# kolrs868_tx_1_4.net
KiCad netlist of a schematic drawn in EAGLE
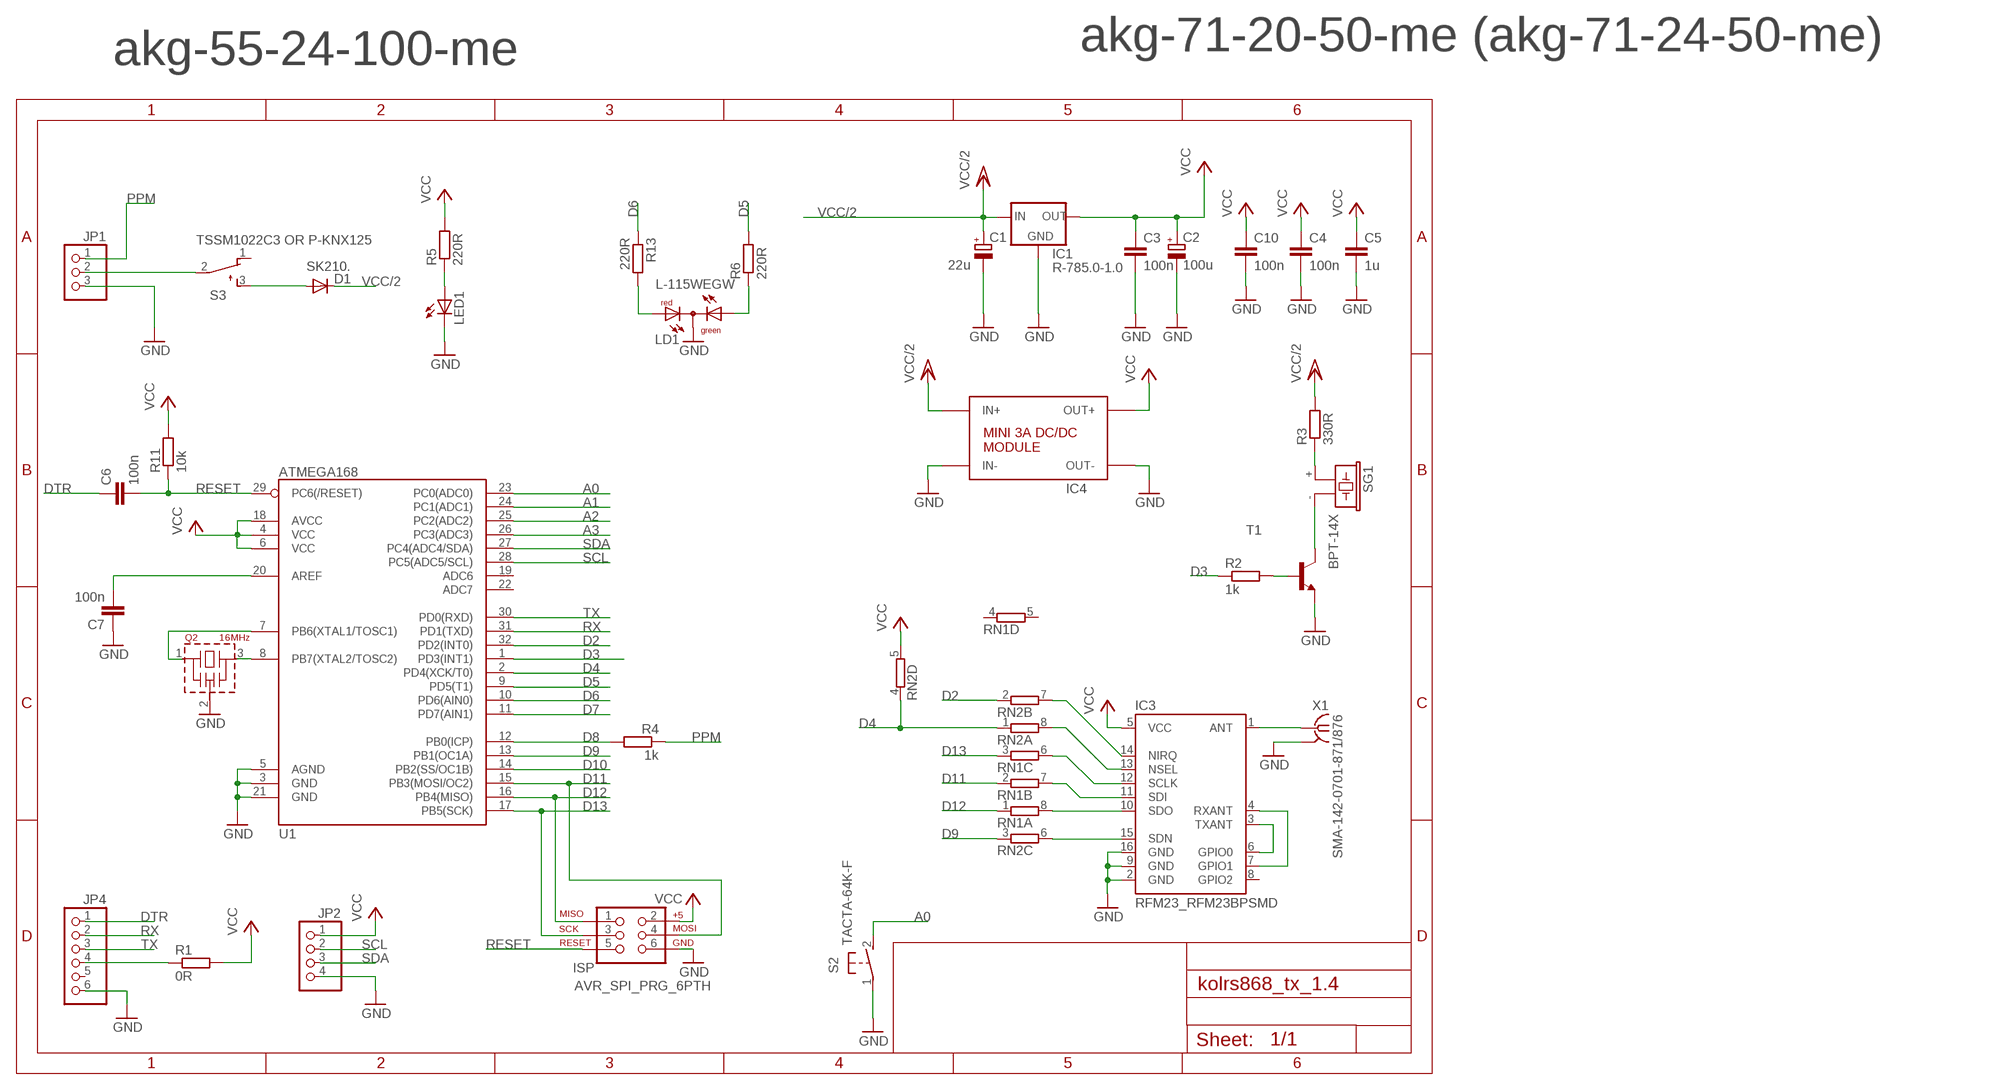
[diagram p0: schematic, sheet 1]

(export (version "E")
  (design (tool "Eeschema 10.0.6"))
  (components
    (comp (ref "C1")
      (value "22u")
      (footprint "eagle-import:SMC_B")
      (libsource (lib "eagle-import") (part "CPOL-EUSMCB"))
    )
    (comp (ref "C2")
      (value "100u")
      (footprint "eagle-import:SMC_B")
      (libsource (lib "eagle-import") (part "CPOL-EUSMCB"))
    )
    (comp (ref "C3")
      (value "100n")
      (footprint "eagle-import:M0805")
      (libsource (lib "eagle-import") (part "C-EU_KOLIN"))
    )
    (comp (ref "C4")
      (value "100n")
      (footprint "eagle-import:M0805")
      (libsource (lib "eagle-import") (part "C-EU_KOLIN"))
    )
    (comp (ref "C5")
      (value "1u")
      (footprint "eagle-import:C1206")
      (libsource (lib "eagle-import") (part "C-EUC1206"))
    )
    (comp (ref "C6")
      (value "100n")
      (footprint "eagle-import:M0805")
      (libsource (lib "eagle-import") (part "C-EU_KOLIN"))
    )
    (comp (ref "C7")
      (value "100n")
      (footprint "eagle-import:M0805")
      (libsource (lib "eagle-import") (part "C-EU_KOLIN"))
    )
    (comp (ref "C10")
      (value "100n")
      (footprint "eagle-import:M0805")
      (libsource (lib "eagle-import") (part "C-EU_KOLIN"))
    )
    (comp (ref "D1")
      (value "SK210.")
      (footprint "eagle-import:SMB")
      (libsource (lib "eagle-import") (part "DIODE-SMB"))
    )
    (comp (ref "IC1")
      (value "R-785.0-1.0")
      (footprint "eagle-import:78XX_RECOM")
      (libsource (lib "eagle-import") (part "78XX_RECOM"))
    )
    (comp (ref "IC3")
      (value "RFM23_RFM23BPSMD")
      (footprint "eagle-import:RFM23_RFM23BP-S2")
      (libsource (lib "eagle-import") (part "RFM23_RFM23BPSMD"))
    )
    (comp (ref "IC4")
      (value "MINI_3A_DCDC")
      (footprint "eagle-import:MINI_3A_DCDC")
      (libsource (lib "eagle-import") (part "MINI_3A_DCDC"))
    )
    (comp (ref "ISP")
      (value "AVR_SPI_PRG_6PTH")
      (footprint "eagle-import:2X3")
      (libsource (lib "eagle-import") (part "AVR_SPI_PRG_6PTH"))
    )
    (comp (ref "JP1")
      (value "PINHD-1X3")
      (footprint "eagle-import:1X03")
      (libsource (lib "eagle-import") (part "PINHD-1X3"))
    )
    (comp (ref "JP2")
      (value "PINHD-1X4")
      (footprint "eagle-import:1X04")
      (libsource (lib "eagle-import") (part "PINHD-1X4"))
    )
    (comp (ref "JP4")
      (value "PINHD-1X6")
      (footprint "eagle-import:1X06")
      (libsource (lib "eagle-import") (part "PINHD-1X6"))
    )
    (comp (ref "LD1")
      (value "L-115WEGW")
      (footprint "eagle-import:DUOLED-C-5MM")
      (libsource (lib "eagle-import") (part "DUOLED-RG-C"))
    )
    (comp (ref "LED1")
      (value "LEDCHIPLED_1206")
      (footprint "eagle-import:CHIPLED_1206")
      (libsource (lib "eagle-import") (part "LEDCHIPLED_1206"))
    )
    (comp (ref "Q2")
      (value "16MHz")
      (footprint "eagle-import:CSTLS_G9")
      (libsource (lib "eagle-import") (part "murata-resonators_CSTLS_G"))
    )
    (comp (ref "R1")
      (value "0R")
      (footprint "eagle-import:M0805")
      (libsource (lib "eagle-import") (part "R-EU_KOLINM0805"))
    )
    (comp (ref "R2")
      (value "1k")
      (footprint "eagle-import:M0805")
      (libsource (lib "eagle-import") (part "R-EU_KOLINM0805"))
    )
    (comp (ref "R3")
      (value "330R")
      (footprint "eagle-import:M0805")
      (libsource (lib "eagle-import") (part "R-EU_KOLINM0805"))
    )
    (comp (ref "R4")
      (value "1k")
      (footprint "eagle-import:M0805")
      (libsource (lib "eagle-import") (part "R-EU_KOLINM0805"))
    )
    (comp (ref "R5")
      (value "220R")
      (footprint "eagle-import:M0805")
      (libsource (lib "eagle-import") (part "R-EU_KOLINM0805"))
    )
    (comp (ref "R6")
      (value "220R")
      (footprint "eagle-import:M0805")
      (libsource (lib "eagle-import") (part "R-EU_KOLINM0805"))
    )
    (comp (ref "R11")
      (value "10k")
      (footprint "eagle-import:M0805")
      (libsource (lib "eagle-import") (part "R-EU_KOLINM0805"))
    )
    (comp (ref "R13")
      (value "220R")
      (footprint "eagle-import:M0805")
      (libsource (lib "eagle-import") (part "R-EU_KOLINM0805"))
    )
    (comp (ref "RN1")
      (value "4R-NCAY16")
      (footprint "eagle-import:CAY16")
      (libsource (lib "eagle-import") (part "4R-NCAY16"))
    )
    (comp (ref "RN2")
      (value "4R-NCAY16")
      (footprint "eagle-import:CAY16")
      (fields (field (name "OC_FARNELL") "unknown") (field (name "OC_NEWARK") "unknown"))
      (libsource (lib "eagle-import") (part "4R-NCAY16"))
    )
    (comp (ref "S2")
      (value "TACTA-64K-F")
      (footprint "eagle-import:B3F-31XX")
      (fields (field (name "MPN") "B3F-3100"))
      (libsource (lib "eagle-import") (part "31-XX"))
    )
    (comp (ref "S3")
      (value "TSSM1022C3 OR P-KNX125")
      (footprint "eagle-import:TL3XWO")
      (libsource (lib "eagle-import") (part "TL32WO"))
    )
    (comp (ref "SG1")
      (value "BPT-14X")
      (footprint "eagle-import:F_CM12P")
      (libsource (lib "eagle-import") (part "F/CM12P"))
    )
    (comp (ref "T1")
      (value "BC848-NPN-SOT23-BEC")
      (footprint "eagle-import:SOT23-BEC")
      (libsource (lib "eagle-import") (part "-NPN-SOT23-BECBC848"))
    )
    (comp (ref "U1")
      (value "ATMEGA168")
      (footprint "eagle-import:TQFP32-08")
      (libsource (lib "eagle-import") (part "ATMEGA168"))
    )
    (comp (ref "X1")
      (value "SMA-142-0701-871/876")
      (footprint "eagle-import:J502-ND-142-0701-871_876")
      (fields (field (name "MF") "JOHNSON COMPONENTS") (field (name "MPN") "142-0701-871"))
      (libsource (lib "eagle-import") (part "SMA-142-0701-871/876"))
    )
  )
  (nets
    (net (code "1") (name "/A0") (class "Default")
      (node (ref "S2") (pin "2") (pinfunction "S_2") (pintype "passive"))
      (node (ref "U1") (pin "23") (pinfunction "PC0(ADC0)_23") (pintype "bidirectional"))
    )
    (net (code "2") (name "/A1") (class "Default")
      (node (ref "U1") (pin "24") (pinfunction "PC1(ADC1)_24") (pintype "bidirectional"))
    )
    (net (code "3") (name "/A2") (class "Default")
      (node (ref "U1") (pin "25") (pinfunction "PC2(ADC2)_25") (pintype "bidirectional"))
    )
    (net (code "4") (name "/A3") (class "Default")
      (node (ref "U1") (pin "26") (pinfunction "PC3(ADC3)_26") (pintype "bidirectional"))
    )
    (net (code "5") (name "/D2") (class "Default")
      (node (ref "RN2") (pin "2") (pinfunction "1_2") (pintype "passive"))
      (node (ref "U1") (pin "32") (pinfunction "PD2(INT0)_32") (pintype "bidirectional"))
    )
    (net (code "6") (name "/D3") (class "Default")
      (node (ref "R2") (pin "1") (pinfunction "1_1") (pintype "passive"))
      (node (ref "U1") (pin "1") (pinfunction "PD3(INT1)_1") (pintype "bidirectional"))
    )
    (net (code "7") (name "/D4") (class "Default")
      (node (ref "RN2") (pin "1") (pinfunction "1_1") (pintype "passive"))
      (node (ref "RN2") (pin "4") (pinfunction "1_4") (pintype "passive"))
      (node (ref "U1") (pin "2") (pinfunction "PD4(XCK/T0)_2") (pintype "bidirectional"))
    )
    (net (code "8") (name "/D5") (class "Default")
      (node (ref "R6") (pin "2") (pinfunction "2_2") (pintype "passive"))
      (node (ref "U1") (pin "9") (pinfunction "PD5(T1)_9") (pintype "bidirectional"))
    )
    (net (code "9") (name "/D6") (class "Default")
      (node (ref "R13") (pin "1") (pinfunction "1_1") (pintype "passive"))
      (node (ref "U1") (pin "10") (pinfunction "PD6(AIN0)_10") (pintype "bidirectional"))
    )
    (net (code "10") (name "/D7") (class "Default")
      (node (ref "U1") (pin "11") (pinfunction "PD7(AIN1)_11") (pintype "bidirectional"))
    )
    (net (code "11") (name "/D8") (class "Default")
      (node (ref "R4") (pin "2") (pinfunction "2_2") (pintype "passive"))
      (node (ref "U1") (pin "12") (pinfunction "PB0(ICP)_12") (pintype "bidirectional"))
    )
    (net (code "12") (name "/D9") (class "Default")
      (node (ref "RN2") (pin "3") (pinfunction "1_3") (pintype "passive"))
      (node (ref "U1") (pin "13") (pinfunction "PB1(OC1A)_13") (pintype "bidirectional"))
    )
    (net (code "13") (name "/D10") (class "Default")
      (node (ref "U1") (pin "14") (pinfunction "PB2(SS/OC1B)_14") (pintype "bidirectional"))
    )
    (net (code "14") (name "/D11") (class "Default")
      (node (ref "ISP") (pin "4") (pinfunction "4_4") (pintype "passive"))
      (node (ref "RN1") (pin "2") (pinfunction "1_2") (pintype "passive"))
      (node (ref "U1") (pin "15") (pinfunction "PB3(MOSI/OC2)_15") (pintype "bidirectional"))
    )
    (net (code "15") (name "/D12") (class "Default")
      (node (ref "ISP") (pin "1") (pinfunction "1_1") (pintype "passive"))
      (node (ref "RN1") (pin "1") (pinfunction "1_1") (pintype "passive"))
      (node (ref "U1") (pin "16") (pinfunction "PB4(MISO)_16") (pintype "bidirectional"))
    )
    (net (code "16") (name "/D13") (class "Default")
      (node (ref "ISP") (pin "3") (pinfunction "3_3") (pintype "passive"))
      (node (ref "RN1") (pin "3") (pinfunction "1_3") (pintype "passive"))
      (node (ref "U1") (pin "17") (pinfunction "PB5(SCK)_17") (pintype "bidirectional"))
    )
    (net (code "17") (name "/DTR") (class "Default")
      (node (ref "C6") (pin "1") (pinfunction "1_1") (pintype "passive"))
      (node (ref "JP4") (pin "1") (pinfunction "1_1") (pintype "passive"))
    )
    (net (code "18") (name "/PPM") (class "Default")
      (node (ref "JP1") (pin "1") (pinfunction "1_1") (pintype "passive"))
      (node (ref "R4") (pin "1") (pinfunction "1_1") (pintype "passive"))
    )
    (net (code "19") (name "/RESET") (class "Default")
      (node (ref "C6") (pin "2") (pinfunction "2_2") (pintype "passive"))
      (node (ref "ISP") (pin "5") (pinfunction "5_5") (pintype "passive"))
      (node (ref "R11") (pin "1") (pinfunction "1_1") (pintype "passive"))
      (node (ref "U1") (pin "29") (pinfunction "PC6(/RESET)_29") (pintype "bidirectional"))
    )
    (net (code "20") (name "/RX") (class "Default")
      (node (ref "JP4") (pin "2") (pinfunction "2_2") (pintype "passive"))
      (node (ref "U1") (pin "31") (pinfunction "PD1(TXD)_31") (pintype "bidirectional"))
    )
    (net (code "21") (name "/SCL") (class "Default")
      (node (ref "JP2") (pin "2") (pinfunction "2_2") (pintype "passive"))
      (node (ref "U1") (pin "28") (pinfunction "PC5(ADC5/SCL)_28") (pintype "bidirectional"))
    )
    (net (code "22") (name "/SDA") (class "Default")
      (node (ref "JP2") (pin "3") (pinfunction "3_3") (pintype "passive"))
      (node (ref "U1") (pin "27") (pinfunction "PC4(ADC4/SDA)_27") (pintype "bidirectional"))
    )
    (net (code "23") (name "/TX") (class "Default")
      (node (ref "JP4") (pin "3") (pinfunction "3_3") (pintype "passive"))
      (node (ref "U1") (pin "30") (pinfunction "PD0(RXD)_30") (pintype "bidirectional"))
    )
    (net (code "24") (name "GND") (class "Default")
      (node (ref "C1") (pin "-") (pinfunction "-_-") (pintype "passive"))
      (node (ref "C10") (pin "2") (pinfunction "2_2") (pintype "passive"))
      (node (ref "C2") (pin "-") (pinfunction "-_-") (pintype "passive"))
      (node (ref "C3") (pin "2") (pinfunction "2_2") (pintype "passive"))
      (node (ref "C4") (pin "2") (pinfunction "2_2") (pintype "passive"))
      (node (ref "C5") (pin "2") (pinfunction "2_2") (pintype "passive"))
      (node (ref "C7") (pin "1") (pinfunction "1_1") (pintype "passive"))
      (node (ref "IC1") (pin "GND") (pinfunction "GND_GND") (pintype "input"))
      (node (ref "IC3") (pin "16") (pinfunction "GND_16") (pintype "power_in"))
      (node (ref "IC3") (pin "2") (pinfunction "GND_2") (pintype "power_in"))
      (node (ref "IC3") (pin "9") (pinfunction "GND_9") (pintype "power_in"))
      (node (ref "IC4") (pin "1") (pinfunction "IN-_1") (pintype "bidirectional"))
      (node (ref "IC4") (pin "2") (pinfunction "IN-_2") (pintype "bidirectional"))
      (node (ref "IC4") (pin "7") (pinfunction "OUT-_7") (pintype "bidirectional"))
      (node (ref "IC4") (pin "8") (pinfunction "OUT-_8") (pintype "bidirectional"))
      (node (ref "ISP") (pin "6") (pinfunction "6_6") (pintype "passive"))
      (node (ref "JP1") (pin "3") (pinfunction "3_3") (pintype "passive"))
      (node (ref "JP2") (pin "4") (pinfunction "4_4") (pintype "passive"))
      (node (ref "JP4") (pin "6") (pinfunction "6_6") (pintype "passive"))
      (node (ref "LD1") (pin "C") (pinfunction "C_C") (pintype "passive"))
      (node (ref "LED1") (pin "C") (pinfunction "C_C") (pintype "passive"))
      (node (ref "Q2") (pin "2") (pinfunction "VSS_2") (pintype "power_in"))
      (node (ref "S2") (pin "1") (pinfunction "P_1") (pintype "passive"))
      (node (ref "T1") (pin "E") (pinfunction "E_E") (pintype "passive"))
      (node (ref "U1") (pin "21") (pinfunction "GND_21") (pintype "bidirectional"))
      (node (ref "U1") (pin "3") (pinfunction "GND_3") (pintype "bidirectional"))
      (node (ref "U1") (pin "5") (pinfunction "AGND_5") (pintype "bidirectional"))
      (node (ref "X1") (pin "G@1") (pinfunction "GND_G@1") (pintype "power_in"))
    )
    (net (code "25") (name "Net-(IC3-ANT)") (class "Default")
      (node (ref "IC3") (pin "1") (pinfunction "ANT_1") (pintype "bidirectional"))
      (node (ref "X1") (pin "1") (pinfunction "1_1") (pintype "passive"))
    )
    (net (code "26") (name "Net-(IC3-GPIO0)") (class "Default")
      (node (ref "IC3") (pin "3") (pinfunction "TXANT_3") (pintype "input"))
      (node (ref "IC3") (pin "6") (pinfunction "GPIO0_6") (pintype "bidirectional"))
    )
    (net (code "27") (name "Net-(IC3-GPIO1)") (class "Default")
      (node (ref "IC3") (pin "4") (pinfunction "RXANT_4") (pintype "input"))
      (node (ref "IC3") (pin "7") (pinfunction "GPIO1_7") (pintype "bidirectional"))
    )
    (net (code "28") (name "Net-(IC3-NIRQ)") (class "Default")
      (node (ref "IC3") (pin "14") (pinfunction "NIRQ_14") (pintype "output"))
      (node (ref "RN2") (pin "7") (pinfunction "2_7") (pintype "passive"))
    )
    (net (code "29") (name "Net-(IC3-NSEL)") (class "Default")
      (node (ref "IC3") (pin "13") (pinfunction "NSEL_13") (pintype "input"))
      (node (ref "RN2") (pin "8") (pinfunction "2_8") (pintype "passive"))
    )
    (net (code "30") (name "Net-(IC3-SCLK)") (class "Default")
      (node (ref "IC3") (pin "12") (pinfunction "SCLK_12") (pintype "input"))
      (node (ref "RN1") (pin "6") (pinfunction "2_6") (pintype "passive"))
    )
    (net (code "31") (name "Net-(IC3-SDI)") (class "Default")
      (node (ref "IC3") (pin "11") (pinfunction "SDI_11") (pintype "input"))
      (node (ref "RN1") (pin "7") (pinfunction "2_7") (pintype "passive"))
    )
    (net (code "32") (name "Net-(IC3-SDN)") (class "Default")
      (node (ref "IC3") (pin "15") (pinfunction "SDN_15") (pintype "input"))
      (node (ref "RN2") (pin "6") (pinfunction "2_6") (pintype "passive"))
    )
    (net (code "33") (name "Net-(IC3-SDO)") (class "Default")
      (node (ref "IC3") (pin "10") (pinfunction "SDO_10") (pintype "output"))
      (node (ref "RN1") (pin "8") (pinfunction "2_8") (pintype "passive"))
    )
    (net (code "34") (name "Net-(JP4-Pad4)") (class "Default")
      (node (ref "JP4") (pin "4") (pinfunction "4_4") (pintype "passive"))
      (node (ref "R1") (pin "1") (pinfunction "1_1") (pintype "passive"))
    )
    (net (code "35") (name "Net-(LD1-AG)") (class "Default")
      (node (ref "LD1") (pin "AX") (pinfunction "AG_AX") (pintype "passive"))
      (node (ref "R6") (pin "1") (pinfunction "1_1") (pintype "passive"))
    )
    (net (code "36") (name "Net-(LD1-PadAR)") (class "Default")
      (node (ref "LD1") (pin "AR") (pinfunction "AR_AR") (pintype "passive"))
      (node (ref "R13") (pin "2") (pinfunction "2_2") (pintype "passive"))
    )
    (net (code "37") (name "Net-(LED1-PadA)") (class "Default")
      (node (ref "LED1") (pin "A") (pinfunction "A_A") (pintype "passive"))
      (node (ref "R5") (pin "1") (pinfunction "1_1") (pintype "passive"))
    )
    (net (code "38") (name "Net-(R2-Pad2)") (class "Default")
      (node (ref "R2") (pin "2") (pinfunction "2_2") (pintype "passive"))
      (node (ref "T1") (pin "B") (pinfunction "B_B") (pintype "passive"))
    )
    (net (code "39") (name "Net-(S3-P)") (class "Default")
      (node (ref "JP1") (pin "2") (pinfunction "2_2") (pintype "passive"))
      (node (ref "S3") (pin "2") (pinfunction "P_2") (pintype "passive"))
    )
    (net (code "40") (name "Net-(S3-S)") (class "Default")
      (node (ref "D1") (pin "A") (pinfunction "A_A") (pintype "passive"))
      (node (ref "S3") (pin "3") (pinfunction "S_3") (pintype "passive"))
    )
    (net (code "41") (name "Net-(SG1-1)") (class "Default")
      (node (ref "R3") (pin "1") (pinfunction "1_1") (pintype "passive"))
      (node (ref "SG1") (pin "+") (pinfunction "1_+") (pintype "passive"))
    )
    (net (code "42") (name "Net-(SG1-2)") (class "Default")
      (node (ref "SG1") (pin "-") (pinfunction "2_-") (pintype "passive"))
      (node (ref "T1") (pin "C") (pinfunction "C_C") (pintype "passive"))
    )
    (net (code "43") (name "Net-(U1-AREF)") (class "Default")
      (node (ref "C7") (pin "2") (pinfunction "2_2") (pintype "passive"))
      (node (ref "U1") (pin "20") (pinfunction "AREF_20") (pintype "bidirectional"))
    )
    (net (code "44") (name "Net-(U1-PB6(XTAL1{slash}TOSC1))") (class "Default")
      (node (ref "Q2") (pin "1") (pinfunction "1_1") (pintype "output"))
      (node (ref "U1") (pin "7") (pinfunction "PB6(XTAL1/TOSC1)_7") (pintype "bidirectional"))
    )
    (net (code "45") (name "Net-(U1-PB7(XTAL2{slash}TOSC2))") (class "Default")
      (node (ref "Q2") (pin "3") (pinfunction "3_3") (pintype "input"))
      (node (ref "U1") (pin "8") (pinfunction "PB7(XTAL2/TOSC2)_8") (pintype "bidirectional"))
    )
    (net (code "46") (name "VCC") (class "Default")
      (node (ref "C10") (pin "1") (pinfunction "1_1") (pintype "passive"))
      (node (ref "C2") (pin "+") (pinfunction "+_+") (pintype "passive"))
      (node (ref "C3") (pin "1") (pinfunction "1_1") (pintype "passive"))
      (node (ref "C4") (pin "1") (pinfunction "1_1") (pintype "passive"))
      (node (ref "C5") (pin "1") (pinfunction "1_1") (pintype "passive"))
      (node (ref "IC1") (pin "OUT") (pinfunction "OUT_OUT") (pintype "passive"))
      (node (ref "IC3") (pin "5") (pinfunction "VCC_5") (pintype "bidirectional"))
      (node (ref "IC4") (pin "5") (pinfunction "OUT+_5") (pintype "bidirectional"))
      (node (ref "IC4") (pin "6") (pinfunction "OUT+_6") (pintype "bidirectional"))
      (node (ref "ISP") (pin "2") (pinfunction "2_2") (pintype "passive"))
      (node (ref "JP2") (pin "1") (pinfunction "1_1") (pintype "passive"))
      (node (ref "R1") (pin "2") (pinfunction "2_2") (pintype "passive"))
      (node (ref "R11") (pin "2") (pinfunction "2_2") (pintype "passive"))
      (node (ref "R5") (pin "2") (pinfunction "2_2") (pintype "passive"))
      (node (ref "RN2") (pin "5") (pinfunction "2_5") (pintype "passive"))
      (node (ref "U1") (pin "18") (pinfunction "AVCC_18") (pintype "bidirectional"))
      (node (ref "U1") (pin "4") (pinfunction "VCC_4") (pintype "bidirectional"))
      (node (ref "U1") (pin "6") (pinfunction "VCC_6") (pintype "bidirectional"))
    )
    (net (code "47") (name "VCC{slash}2") (class "Default")
      (node (ref "C1") (pin "+") (pinfunction "+_+") (pintype "passive"))
      (node (ref "D1") (pin "C") (pinfunction "C_C") (pintype "passive"))
      (node (ref "IC1") (pin "IN") (pinfunction "IN_IN") (pintype "input"))
      (node (ref "IC4") (pin "3") (pinfunction "IN+_3") (pintype "bidirectional"))
      (node (ref "IC4") (pin "4") (pinfunction "IN+_4") (pintype "bidirectional"))
      (node (ref "R3") (pin "2") (pinfunction "2_2") (pintype "passive"))
    )
    (net (code "48") (name "unconnected-(IC3-GPIO2-Pad8)") (class "Default")
      (node (ref "IC3") (pin "8") (pinfunction "GPIO2_8") (pintype "bidirectional"))
    )
    (net (code "49") (name "unconnected-(JP4-Pad5)") (class "Default")
      (node (ref "JP4") (pin "5") (pinfunction "5_5") (pintype "passive"))
    )
    (net (code "50") (name "unconnected-(RN1D-1-Pad4)") (class "Default")
      (node (ref "RN1") (pin "4") (pinfunction "1_4") (pintype "passive"))
    )
    (net (code "51") (name "unconnected-(RN1D-2-Pad5)") (class "Default")
      (node (ref "RN1") (pin "5") (pinfunction "2_5") (pintype "passive"))
    )
    (net (code "52") (name "unconnected-(S3-O-Pad1)") (class "Default")
      (node (ref "S3") (pin "1") (pinfunction "O_1") (pintype "passive"))
    )
    (net (code "53") (name "unconnected-(U1-ADC6-Pad19)") (class "Default")
      (node (ref "U1") (pin "19") (pinfunction "ADC6_19") (pintype "bidirectional"))
    )
    (net (code "54") (name "unconnected-(U1-ADC7-Pad22)") (class "Default")
      (node (ref "U1") (pin "22") (pinfunction "ADC7_22") (pintype "bidirectional"))
    )
  )
)
